# Sheet1.net
KiCad netlist of a schematic drawn in Altium Designer
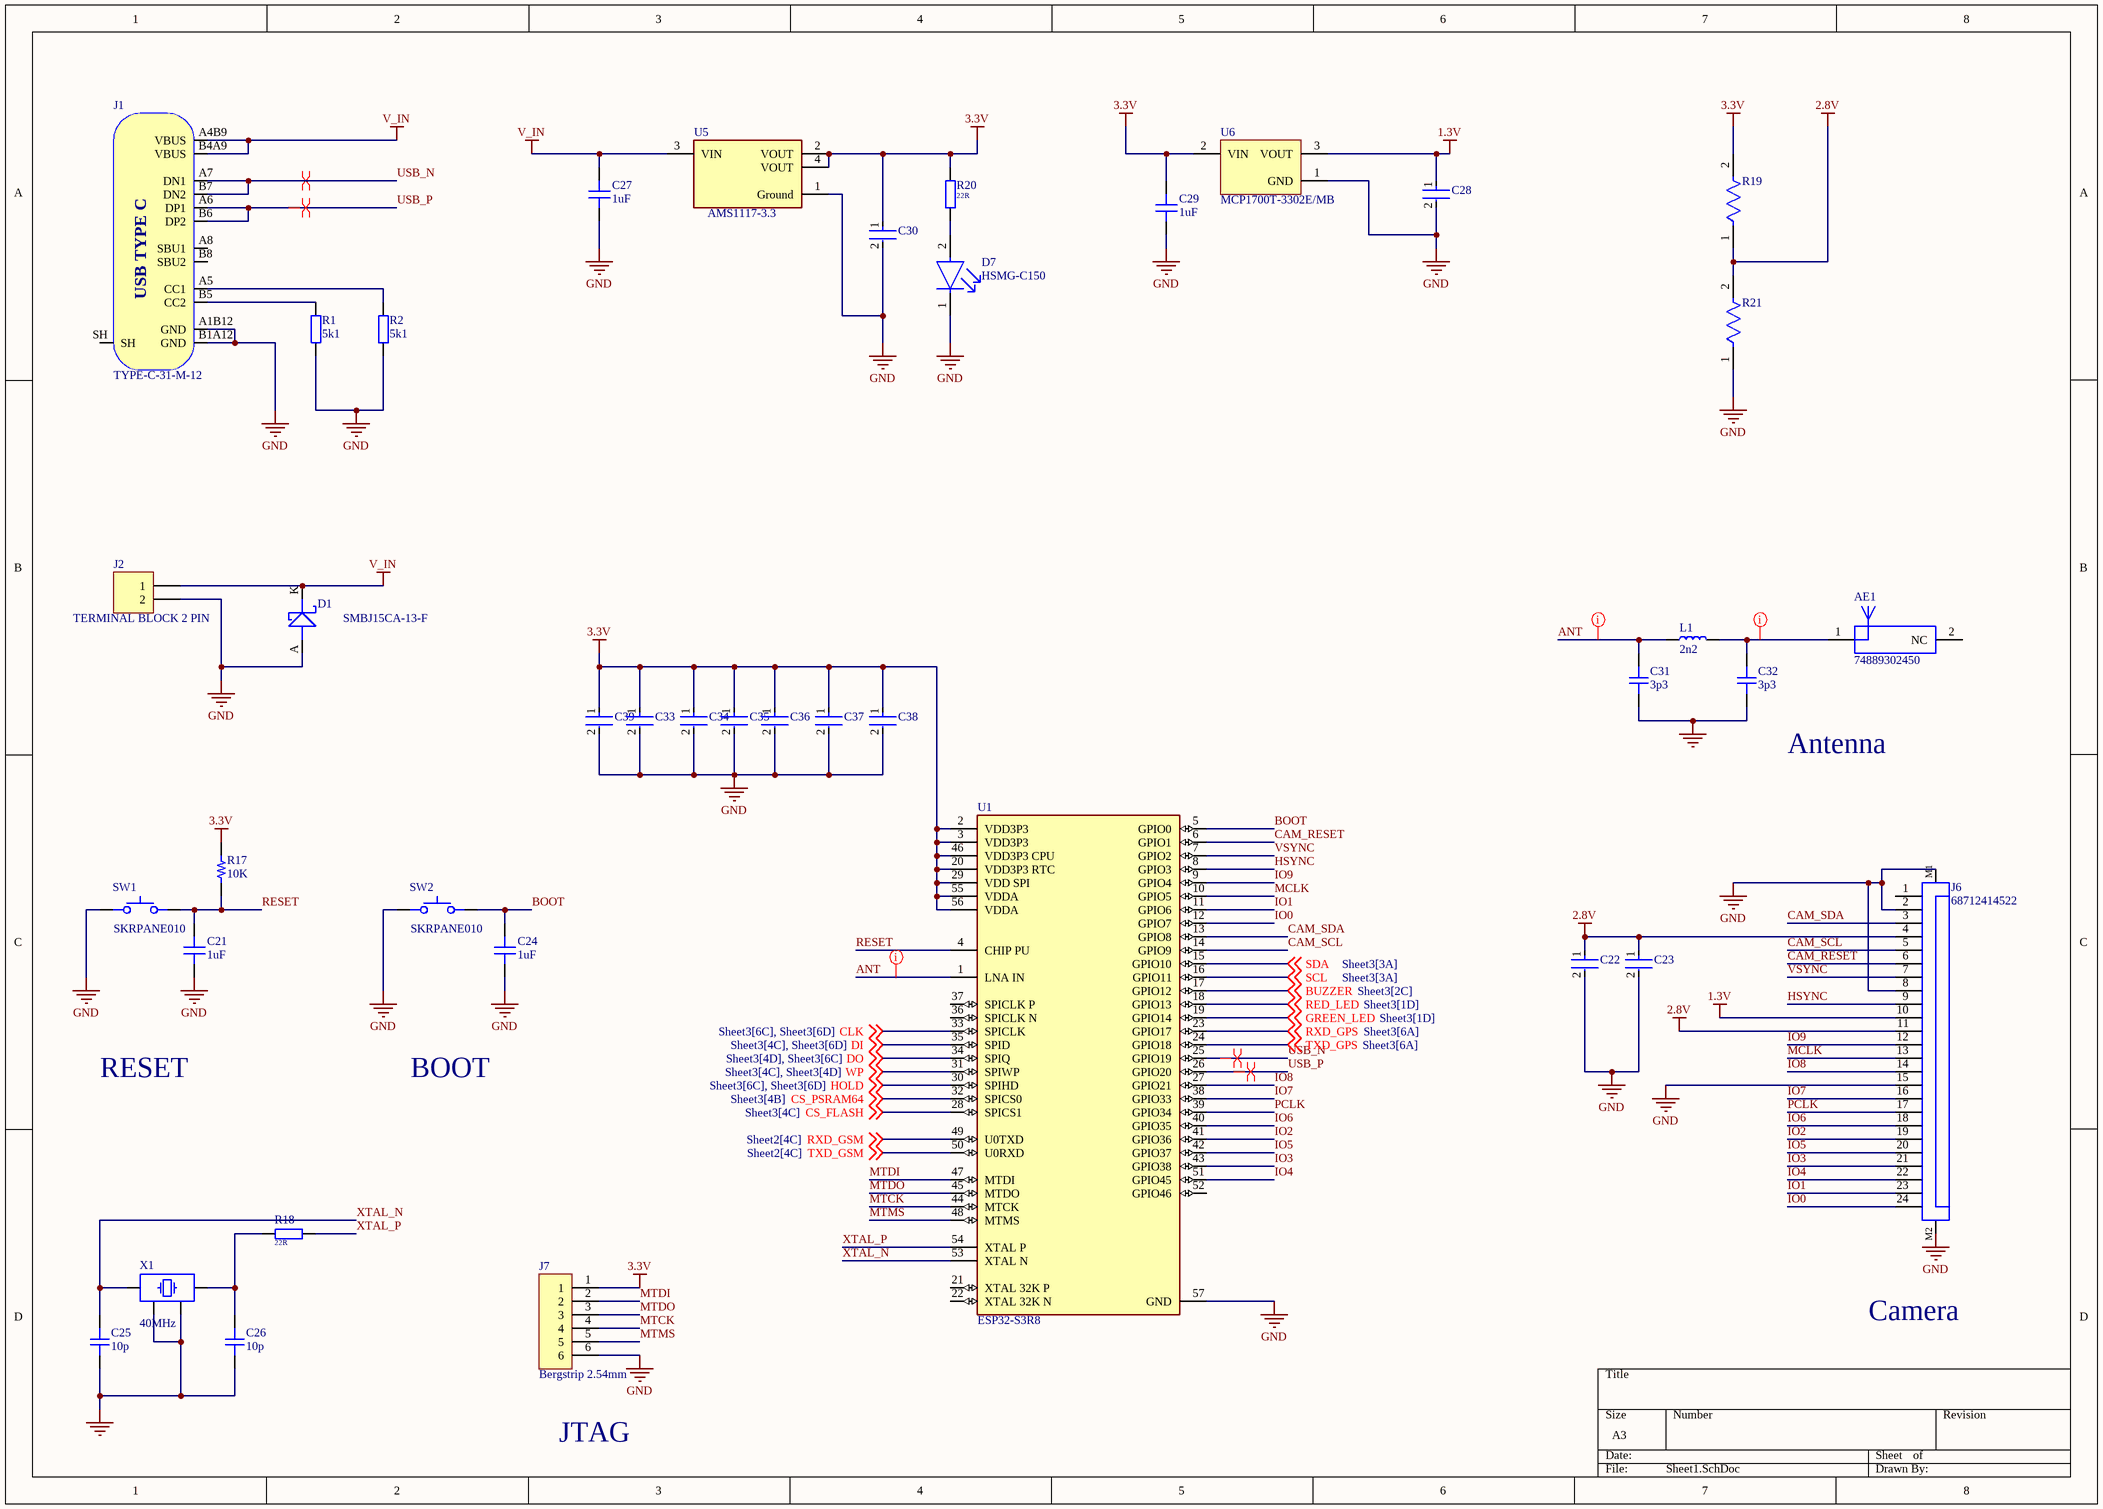
[diagram p0: Sheet1.SchDoc]

(export (version "E")
  (design (tool "Eeschema 10.0.6"))
  (components
    (comp (ref "AE1")
      (value "74889302450")
      (footprint "74889302450")
      (description "74889302450 Chip Antenna, 2.45Ghz, 3.2Mm X 1.6Mm X 1.2Mm Rohs Compliant: Yes")
      (libsource (lib "Altium Content Vault") (part "74889302450"))
    )
    (comp (ref "C21")
      (value "1uF")
      (footprint "CAP 0402_1005")
      (description "SMT Capacitor")
      (libsource (lib "Capacitor") (part "Cap 0402"))
    )
    (comp (ref "C22")
      (value "C0402C104K4RACTU")
      (footprint "FP-C0402-BB-MFG")
      (description "CAP CER 0.1UF 16V X7R 0402")
      (fields
        (field (name "TOLERANCE") "0.1")
        (field (name "OCTOPART") "https://octopart.com/c0402c104k4ractu-kemet-94158")
      )
      (libsource (lib "Altium Content Vault") (part "b4654b650e69147ec39a6b967a45e02"))
    )
    (comp (ref "C23")
      (value "C0402C104K4RACTU")
      (footprint "FP-C0402-BB-MFG")
      (description "CAP CER 0.1UF 16V X7R 0402")
      (fields
        (field (name "TOLERANCE") "0.1")
        (field (name "OCTOPART") "https://octopart.com/c0402c104k4ractu-kemet-94158")
      )
      (libsource (lib "Altium Content Vault") (part "b4654b650e69147ec39a6b967a45e02"))
    )
    (comp (ref "C24")
      (value "1uF")
      (footprint "CAP 0402_1005")
      (description "SMT Capacitor")
      (libsource (lib "Capacitor") (part "Cap 0402"))
    )
    (comp (ref "C25")
      (value "10p")
      (footprint "CAP_0402")
      (description "Capacitor SMD 0402 50V")
      (fields
        (field (name "MANUFACTURER") "Samsung")
        (field (name "MANUFACTURER PART NUMBER") "CL05C100JB5NNNC")
      )
      (libsource (lib "Schematic-Lib-PhilsLab") (part "CAP_0402_50V"))
    )
    (comp (ref "C26")
      (value "10p")
      (footprint "CAP_0402")
      (description "Capacitor SMD 0402 50V")
      (fields
        (field (name "MANUFACTURER") "Samsung")
        (field (name "MANUFACTURER PART NUMBER") "CL05C100JB5NNNC")
      )
      (libsource (lib "Schematic-Lib-PhilsLab") (part "CAP_0402_50V"))
    )
    (comp (ref "C27")
      (value "1uF")
      (footprint "CAP 0402_1005")
      (description "SMT Capacitor")
      (libsource (lib "Capacitor") (part "Cap 0402"))
    )
    (comp (ref "C28")
      (value "C0402C104K4RACTU")
      (footprint "FP-C0402-BB-MFG")
      (description "CAP CER 0.1UF 16V X7R 0402")
      (fields
        (field (name "TOLERANCE") "0.1")
        (field (name "OCTOPART") "https://octopart.com/c0402c104k4ractu-kemet-94158")
      )
      (libsource (lib "Altium Content Vault") (part "b4654b650e69147ec39a6b967a45e02"))
    )
    (comp (ref "C29")
      (value "1uF")
      (footprint "CAP 0402_1005")
      (description "SMT Capacitor")
      (libsource (lib "Capacitor") (part "Cap 0402"))
    )
    (comp (ref "C30")
      (value "C0402C104K4RACTU")
      (footprint "FP-C0402-BB-MFG")
      (description "CAP CER 0.1UF 16V X7R 0402")
      (fields
        (field (name "TOLERANCE") "0.1")
        (field (name "OCTOPART") "https://octopart.com/c0402c104k4ractu-kemet-94158")
      )
      (libsource (lib "Altium Content Vault") (part "b4654b650e69147ec39a6b967a45e02"))
    )
    (comp (ref "C31")
      (value "3p3")
      (footprint "CAP_0402")
      (description "Capacitor SMD 0402 50V")
      (fields (field (name "MANUFACTURER") "FH") (field (name "MANUFACTURER PART NUMBER") "0402CG3R3C500NT"))
      (libsource (lib "Schematic-Lib-PhilsLab") (part "CAP_0402_50V"))
    )
    (comp (ref "C32")
      (value "3p3")
      (footprint "CAP_0402")
      (description "Capacitor SMD 0402 50V")
      (fields (field (name "MANUFACTURER") "FH") (field (name "MANUFACTURER PART NUMBER") "0402CG3R3C500NT"))
      (libsource (lib "Schematic-Lib-PhilsLab") (part "CAP_0402_50V"))
    )
    (comp (ref "C33")
      (value "C0402C104K4RACTU")
      (footprint "FP-C0402-BB-MFG")
      (description "CAP CER 0.1UF 16V X7R 0402")
      (fields
        (field (name "TOLERANCE") "0.1")
        (field (name "OCTOPART") "https://octopart.com/c0402c104k4ractu-kemet-94158")
      )
      (libsource (lib "Altium Content Vault") (part "b4654b650e69147ec39a6b967a45e02"))
    )
    (comp (ref "C34")
      (value "C0402C104K4RACTU")
      (footprint "FP-C0402-BB-MFG")
      (description "CAP CER 0.1UF 16V X7R 0402")
      (fields
        (field (name "TOLERANCE") "0.1")
        (field (name "OCTOPART") "https://octopart.com/c0402c104k4ractu-kemet-94158")
      )
      (libsource (lib "Altium Content Vault") (part "b4654b650e69147ec39a6b967a45e02"))
    )
    (comp (ref "C35")
      (value "C0402C104K4RACTU")
      (footprint "FP-C0402-BB-MFG")
      (description "CAP CER 0.1UF 16V X7R 0402")
      (fields
        (field (name "TOLERANCE") "0.1")
        (field (name "OCTOPART") "https://octopart.com/c0402c104k4ractu-kemet-94158")
      )
      (libsource (lib "Altium Content Vault") (part "b4654b650e69147ec39a6b967a45e02"))
    )
    (comp (ref "C36")
      (value "C0402C104K4RACTU")
      (footprint "FP-C0402-BB-MFG")
      (description "CAP CER 0.1UF 16V X7R 0402")
      (fields
        (field (name "TOLERANCE") "0.1")
        (field (name "OCTOPART") "https://octopart.com/c0402c104k4ractu-kemet-94158")
      )
      (libsource (lib "Altium Content Vault") (part "b4654b650e69147ec39a6b967a45e02"))
    )
    (comp (ref "C37")
      (value "C0402C104K4RACTU")
      (footprint "FP-C0402-BB-MFG")
      (description "CAP CER 0.1UF 16V X7R 0402")
      (fields
        (field (name "TOLERANCE") "0.1")
        (field (name "OCTOPART") "https://octopart.com/c0402c104k4ractu-kemet-94158")
      )
      (libsource (lib "Altium Content Vault") (part "b4654b650e69147ec39a6b967a45e02"))
    )
    (comp (ref "C38")
      (value "C0402C104K4RACTU")
      (footprint "FP-C0402-BB-MFG")
      (description "CAP CER 0.1UF 16V X7R 0402")
      (fields
        (field (name "TOLERANCE") "0.1")
        (field (name "OCTOPART") "https://octopart.com/c0402c104k4ractu-kemet-94158")
      )
      (libsource (lib "Altium Content Vault") (part "b4654b650e69147ec39a6b967a45e02"))
    )
    (comp (ref "C39")
      (value "C0402C104K4RACTU")
      (footprint "FP-C0402-BB-MFG")
      (description "CAP CER 0.1UF 16V X7R 0402")
      (fields
        (field (name "TOLERANCE") "0.1")
        (field (name "OCTOPART") "https://octopart.com/c0402c104k4ractu-kemet-94158")
      )
      (libsource (lib "Altium Content Vault") (part "b4654b650e69147ec39a6b967a45e02"))
    )
    (comp (ref "D1")
      (value "SMBJ15CA-13-F")
      (footprint "DIO_SMB_DO-214AA")
      (description "24.4V Clamp 24.6A Ipp Tvs Diode Surface Mount DO-214AA (SMBJ)")
      (fields (field (name "MANUFACTURER") "Nexperia"))
      (libsource (lib "ESTEEMPCBLIB") (part "DIO-T_15V-24V-24.6A-DO214AA"))
    )
    (comp (ref "D7")
      (value "HSMG-C150")
      (footprint "FP-HSMG-C150-MFG")
      (description "LED GREEN DIFFUSED 1206 SMD")
      (fields
        (field (name "MANUFACTURER") "Broadcom")
        (field (name "OCTOPART") "https://octopart.com/hsmg-c150-broadcom-71131304")
      )
      (libsource (lib "Altium Content Vault") (part "8706943c75ba83719d021d2fdc84c58"))
    )
    (comp (ref "J1")
      (value "TYPE-C-31-M-12")
      (footprint "TYPE-C-31-M-12")
      (description "USB Type C Connector Horizontal SMT")
      (fields (field (name "MANUFACTURER") "Koren Hroparts"))
      (libsource (lib "ESP32_USB_Dongle") (part "TYPE-C-31-M-12"))
    )
    (comp (ref "J2")
      (value "TERMINAL BLOCK 2 PIN")
      (footprint "CON2_P196_1729128_TH_ST")
      (description "2 Pins, 1 Row 5mm Pitch, straight Connector, male")
      (fields
        (field (name "MANUFACTURER") "Phoenix Contact")
        (field (name "MANUFACTURER PART NUMBER") "MKDSN1,5/2")
      )
      (libsource (lib "ESTEEMPCBLIB") (part "CON-TB_2X1-196-ST-TH"))
    )
    (comp (ref "J6")
      (value "68712414522")
      (footprint "68712414522")
      (libsource (lib "Altium Content Vault") (part "FPC - 24P - 2MP"))
    )
    (comp (ref "J7")
      (value "Bergstrip 2.54mm")
      (footprint "CON6_100_59D78_TH_ST")
      (description "6 Pins, 1 Row 2.54mm Pitch, Straight bergstrip, Female")
      (fields (field (name "MANUFACTURER") "Molex") (field (name "MANUFACTURER PART NUMBER") "22-10-2061"))
      (libsource (lib "ESTEEMPCBLIB") (part "CON-BS-SKT_6X1-100-ST-TH"))
    )
    (comp (ref "L1")
      (value "2n2")
      (footprint "IND_0402")
      (description "Inductor SMD 0402")
      (fields
        (field (name "MANUFACTURER") "Murata")
        (field (name "MANUFACTURER PART NUMBER") "LQW15AN2N2G80D")
      )
      (libsource (lib "Schematic-Lib-PhilsLab") (part "IND_0402"))
    )
    (comp (ref "R1")
      (value "5k1")
      (footprint "RES_0402")
      (description "Resistor SMD 0402")
      (fields
        (field (name "MANUFACTURER") "YAGEO")
        (field (name "MANUFACTURER PART NUMBER") "RC0402JR-075K1L")
      )
      (libsource (lib "ESP32_USB_Dongle") (part "RES_0402"))
    )
    (comp (ref "R2")
      (value "5k1")
      (footprint "RES_0402")
      (description "Resistor SMD 0402")
      (fields
        (field (name "MANUFACTURER") "YAGEO")
        (field (name "MANUFACTURER PART NUMBER") "RC0402JR-075K1L")
      )
      (libsource (lib "ESP32_USB_Dongle") (part "RES_0402"))
    )
    (comp (ref "R17")
      (value "10K")
      (footprint "RES 0402_1005")
      (description "SMT Resistor")
      (libsource (lib "Resistor") (part "Res 0402"))
    )
    (comp (ref "R18")
      (value "22R")
      (footprint "RES_0402")
      (description "Resistor SMD 0402")
      (fields
        (field (name "MANUFACTURER") "UNI-ROYAL")
        (field (name "MANUFACTURER PART NUMBER") "0402WGF220JTCE")
      )
      (libsource (lib "Schematic-Lib-PhilsLab") (part "RES_0402"))
    )
    (comp (ref "R19")
      (value "CRCW06031K00FKEA")
      (footprint "FP-CRCW0603-e3-MFG")
      (description "RES Thick Film, 1kΩ, 1%, 0.1W, 100ppm/°C, 0603")
      (fields (field (name "TOLERANCE") "1%"))
      (libsource (lib "Altium Content Vault") (part "1029c3af85768c4190bb7ad29bc67b5"))
    )
    (comp (ref "R20")
      (value "22R")
      (footprint "RES_0402")
      (description "Resistor SMD 0402")
      (fields
        (field (name "MANUFACTURER") "UNI-ROYAL")
        (field (name "MANUFACTURER PART NUMBER") "0402WGF220JTCE")
      )
      (libsource (lib "Schematic-Lib-PhilsLab") (part "RES_0402"))
    )
    (comp (ref "R21")
      (value "CRCW06035K60FKEA")
      (footprint "FP-CRCW0603-e3-MFG")
      (description "RES Thick Film, 5.6kΩ, 1%, 0.1W, 100ppm/°C, 0603")
      (fields (field (name "TOLERANCE") "1%"))
      (libsource (lib "Altium Content Vault") (part "1029c3af85768c4190bb7ad29bc67b5"))
    )
    (comp (ref "SW1")
      (value "SKRPANE010")
      (footprint "SKRPANE010")
      (description "Tactile Switch SMD SPST")
      (fields (field (name "MANUFACTURER") "Alps Alpine"))
      (libsource (lib "ESP32_USB_Dongle") (part "SKRPANE010"))
    )
    (comp (ref "SW2")
      (value "SKRPANE010")
      (footprint "SKRPANE010")
      (description "Tactile Switch SMD SPST")
      (fields (field (name "MANUFACTURER") "Alps Alpine"))
      (libsource (lib "ESP32_USB_Dongle") (part "SKRPANE010"))
    )
    (comp (ref "U1")
      (value "ESP32-S3R8")
      (footprint "FP-ESP32-S3R8-IPC_A")
      (description "ESP32-S3R8 RF System on a Chip - SoC SMD IC, Dual-Core MCU, Wi-Fi 2.4G BLE 5.0 Combo")
      (libsource (lib "Altium Content Vault") (part "a095f160bb9f313373d963ad131b0ed"))
    )
    (comp (ref "U5")
      (value "AMS1117-3.3")
      (footprint "FP-AMS1117-IPC_C")
      (description "LDO Voltage Regulators 1A, 3.3V")
      (fields
        (field (name "OCTOPART") "https://octopart.com/ams1117-3.3-advanced+monolithic+systems-25899300")
        (field (name "MANUFACTURER") "Advanced Monolithic Systems")
      )
      (libsource (lib "Altium Content Vault") (part "8bdbb5f8e77002000e30dd2845d0354"))
    )
    (comp (ref "U6")
      (value "MCP1700T-3302E/MB")
      (footprint "SOT-89-MB3_M")
      (description "Low Quiescent Current LDO, 3-Pin SOT-89, Extended Temperature, Tape and Reel")
      (libsource (lib "Altium Content Vault") (part "PM-LINEREG-MCP1700-IL3A"))
    )
    (comp (ref "X1")
      (value "40MHz")
      (footprint "XTAL_2520")
      (description "Crystal SMD 2520")
      (fields (field (name "MANUFACTURER") "Seiko Epson"))
      (libsource (lib "Schematic-Lib-PhilsLab") (part "XTAL_2520"))
    )
  )
  (nets
    (net (code "1") (name "/ANT") (class "Default")
      (node (ref "C31") (pin "2") (pinfunction "2_2") (pintype "passive"))
      (node (ref "L1") (pin "2") (pinfunction "2_2") (pintype "passive"))
      (node (ref "U1") (pin "1") (pinfunction "LNA_IN_1") (pintype "passive"))
    )
    (net (code "2") (name "/BOOT") (class "Default")
      (node (ref "C24") (pin "2") (pinfunction "2_2") (pintype "passive"))
      (node (ref "SW2") (pin "34") (pintype "passive"))
      (node (ref "U1") (pin "5") (pinfunction "GPIO0_5") (pintype "bidirectional"))
    )
    (net (code "3") (name "/CAM_RESET") (class "Default")
      (node (ref "J6") (pin "6") (pinfunction "6_6") (pintype "passive"))
      (node (ref "U1") (pin "6") (pinfunction "GPIO1_6") (pintype "bidirectional"))
    )
    (net (code "4") (name "/CAM_SCL") (class "Default")
      (node (ref "J6") (pin "5") (pinfunction "5_5") (pintype "passive"))
      (node (ref "U1") (pin "14") (pinfunction "GPIO9_14") (pintype "bidirectional"))
    )
    (net (code "5") (name "/CAM_SDA") (class "Default")
      (node (ref "J6") (pin "3") (pinfunction "3_3") (pintype "passive"))
      (node (ref "U1") (pin "13") (pinfunction "GPIO8_13") (pintype "bidirectional"))
    )
    (net (code "6") (name "/HSYNC") (class "Default")
      (node (ref "J6") (pin "9") (pinfunction "9_9") (pintype "passive"))
      (node (ref "U1") (pin "8") (pinfunction "GPIO3_8") (pintype "bidirectional"))
    )
    (net (code "7") (name "/IO0") (class "Default")
      (node (ref "J6") (pin "24") (pinfunction "24_24") (pintype "passive"))
      (node (ref "U1") (pin "12") (pinfunction "GPIO7_12") (pintype "bidirectional"))
    )
    (net (code "8") (name "/IO1") (class "Default")
      (node (ref "J6") (pin "23") (pinfunction "23_23") (pintype "passive"))
      (node (ref "U1") (pin "11") (pinfunction "GPIO6_11") (pintype "bidirectional"))
    )
    (net (code "9") (name "/IO2") (class "Default")
      (node (ref "J6") (pin "19") (pinfunction "19_19") (pintype "passive"))
      (node (ref "U1") (pin "41") (pinfunction "GPIO36_41") (pintype "bidirectional"))
    )
    (net (code "10") (name "/IO3") (class "Default")
      (node (ref "J6") (pin "21") (pinfunction "21_21") (pintype "passive"))
      (node (ref "U1") (pin "43") (pinfunction "GPIO38_43") (pintype "bidirectional"))
    )
    (net (code "11") (name "/IO4") (class "Default")
      (node (ref "J6") (pin "22") (pinfunction "22_22") (pintype "passive"))
      (node (ref "U1") (pin "51") (pinfunction "GPIO45_51") (pintype "bidirectional"))
    )
    (net (code "12") (name "/IO5") (class "Default")
      (node (ref "J6") (pin "20") (pinfunction "20_20") (pintype "passive"))
      (node (ref "U1") (pin "42") (pinfunction "GPIO37_42") (pintype "bidirectional"))
    )
    (net (code "13") (name "/IO6") (class "Default")
      (node (ref "J6") (pin "18") (pinfunction "18_18") (pintype "passive"))
      (node (ref "U1") (pin "40") (pinfunction "GPIO35_40") (pintype "bidirectional"))
    )
    (net (code "14") (name "/IO7") (class "Default")
      (node (ref "J6") (pin "16") (pinfunction "16_16") (pintype "passive"))
      (node (ref "U1") (pin "38") (pinfunction "GPIO33_38") (pintype "bidirectional"))
    )
    (net (code "15") (name "/IO8") (class "Default")
      (node (ref "J6") (pin "14") (pinfunction "14_14") (pintype "passive"))
      (node (ref "U1") (pin "27") (pinfunction "GPIO21_27") (pintype "bidirectional"))
    )
    (net (code "16") (name "/IO9") (class "Default")
      (node (ref "J6") (pin "12") (pinfunction "12_12") (pintype "passive"))
      (node (ref "U1") (pin "9") (pinfunction "GPIO4_9") (pintype "bidirectional"))
    )
    (net (code "17") (name "/MCLK") (class "Default")
      (node (ref "J6") (pin "13") (pinfunction "13_13") (pintype "passive"))
      (node (ref "U1") (pin "10") (pinfunction "GPIO5_10") (pintype "bidirectional"))
    )
    (net (code "18") (name "/MTCK") (class "Default")
      (node (ref "J7") (pin "4") (pinfunction "4_4") (pintype "passive"))
      (node (ref "U1") (pin "44") (pinfunction "MTCK_44") (pintype "bidirectional"))
    )
    (net (code "19") (name "/MTDI") (class "Default")
      (node (ref "J7") (pin "2") (pinfunction "2_2") (pintype "passive"))
      (node (ref "U1") (pin "47") (pinfunction "MTDI_47") (pintype "bidirectional"))
    )
    (net (code "20") (name "/MTDO") (class "Default")
      (node (ref "J7") (pin "3") (pinfunction "3_3") (pintype "passive"))
      (node (ref "U1") (pin "45") (pinfunction "MTDO_45") (pintype "bidirectional"))
    )
    (net (code "21") (name "/MTMS") (class "Default")
      (node (ref "J7") (pin "5") (pinfunction "5_5") (pintype "passive"))
      (node (ref "U1") (pin "48") (pinfunction "MTMS_48") (pintype "bidirectional"))
    )
    (net (code "22") (name "/PCLK") (class "Default")
      (node (ref "J6") (pin "17") (pinfunction "17_17") (pintype "passive"))
      (node (ref "U1") (pin "39") (pinfunction "GPIO34_39") (pintype "bidirectional"))
    )
    (net (code "23") (name "/RESET") (class "Default")
      (node (ref "C21") (pin "2") (pinfunction "2_2") (pintype "passive"))
      (node (ref "R17") (pin "1") (pinfunction "1_1") (pintype "passive"))
      (node (ref "SW1") (pin "34") (pintype "passive"))
      (node (ref "U1") (pin "4") (pinfunction "CHIP_PU_4") (pintype "passive"))
    )
    (net (code "24") (name "/USB_N") (class "Default")
      (node (ref "J1") (pin "A7") (pinfunction "DN1_A7") (pintype "bidirectional"))
      (node (ref "J1") (pin "B7") (pinfunction "DN2_B7") (pintype "bidirectional"))
      (node (ref "U1") (pin "25") (pinfunction "GPIO19_25") (pintype "bidirectional"))
    )
    (net (code "25") (name "/USB_P") (class "Default")
      (node (ref "J1") (pin "A6") (pinfunction "DP1_A6") (pintype "bidirectional"))
      (node (ref "J1") (pin "B6") (pinfunction "DP2_B6") (pintype "bidirectional"))
      (node (ref "U1") (pin "26") (pinfunction "GPIO20_26") (pintype "bidirectional"))
    )
    (net (code "26") (name "/VSYNC") (class "Default")
      (node (ref "J6") (pin "7") (pinfunction "7_7") (pintype "passive"))
      (node (ref "U1") (pin "7") (pinfunction "GPIO2_7") (pintype "bidirectional"))
    )
    (net (code "27") (name "/XTAL_N") (class "Default")
      (node (ref "C25") (pin "2") (pinfunction "2_2") (pintype "passive"))
      (node (ref "U1") (pin "53") (pinfunction "XTAL_N_53") (pintype "passive"))
      (node (ref "X1") (pin "1") (pinfunction "1_1") (pintype "passive"))
    )
    (net (code "28") (name "/XTAL_P") (class "Default")
      (node (ref "R18") (pin "1") (pinfunction "1_1") (pintype "passive"))
      (node (ref "U1") (pin "54") (pinfunction "XTAL_P_54") (pintype "passive"))
    )
    (net (code "29") (name "1.3V") (class "Default")
      (node (ref "C28") (pin "1") (pinfunction "1_1") (pintype "passive"))
      (node (ref "J6") (pin "10") (pinfunction "10_10") (pintype "passive"))
      (node (ref "U6") (pin "3") (pinfunction "VOUT_3") (pintype "power_in"))
    )
    (net (code "30") (name "2.8V") (class "Default")
      (node (ref "C22") (pin "1") (pinfunction "1_1") (pintype "passive"))
      (node (ref "C23") (pin "1") (pinfunction "1_1") (pintype "passive"))
      (node (ref "J6") (pin "11") (pinfunction "11_11") (pintype "passive"))
      (node (ref "J6") (pin "4") (pinfunction "4_4") (pintype "passive"))
      (node (ref "R19") (pin "1") (pinfunction "1_1") (pintype "passive"))
      (node (ref "R21") (pin "2") (pinfunction "2_2") (pintype "passive"))
    )
    (net (code "31") (name "3.3V") (class "Default")
      (node (ref "C29") (pin "2") (pinfunction "2_2") (pintype "passive"))
      (node (ref "C30") (pin "1") (pinfunction "1_1") (pintype "passive"))
      (node (ref "C33") (pin "1") (pinfunction "1_1") (pintype "passive"))
      (node (ref "C34") (pin "1") (pinfunction "1_1") (pintype "passive"))
      (node (ref "C35") (pin "1") (pinfunction "1_1") (pintype "passive"))
      (node (ref "C36") (pin "1") (pinfunction "1_1") (pintype "passive"))
      (node (ref "C37") (pin "1") (pinfunction "1_1") (pintype "passive"))
      (node (ref "C38") (pin "1") (pinfunction "1_1") (pintype "passive"))
      (node (ref "C39") (pin "1") (pinfunction "1_1") (pintype "passive"))
      (node (ref "J7") (pin "1") (pinfunction "1_1") (pintype "passive"))
      (node (ref "R17") (pin "2") (pinfunction "2_2") (pintype "passive"))
      (node (ref "R19") (pin "2") (pinfunction "2_2") (pintype "passive"))
      (node (ref "R20") (pin "1") (pinfunction "1_1") (pintype "passive"))
      (node (ref "U1") (pin "2") (pinfunction "VDD3P3_2") (pintype "power_in"))
      (node (ref "U1") (pin "20") (pinfunction "VDD3P3_RTC_20") (pintype "power_in"))
      (node (ref "U1") (pin "29") (pinfunction "VDD_SPI_29") (pintype "power_in"))
      (node (ref "U1") (pin "3") (pinfunction "VDD3P3_3") (pintype "power_in"))
      (node (ref "U1") (pin "46") (pinfunction "VDD3P3_CPU_46") (pintype "power_in"))
      (node (ref "U1") (pin "55") (pinfunction "VDDA_55") (pintype "power_in"))
      (node (ref "U1") (pin "56") (pinfunction "VDDA_56") (pintype "power_in"))
      (node (ref "U5") (pin "2") (pinfunction "VOUT_2") (pintype "passive"))
      (node (ref "U5") (pin "4") (pinfunction "VOUT_4") (pintype "passive"))
      (node (ref "U6") (pin "2") (pinfunction "VIN_2") (pintype "power_in"))
    )
    (net (code "32") (name "BUZZER") (class "Default")
      (node (ref "U1") (pin "17") (pinfunction "GPIO12_17") (pintype "bidirectional"))
    )
    (net (code "33") (name "CLK") (class "Default")
      (node (ref "U1") (pin "33") (pinfunction "SPICLK_33") (pintype "bidirectional"))
    )
    (net (code "34") (name "CS_FLASH") (class "Default")
      (node (ref "U1") (pin "28") (pinfunction "SPICS1_28") (pintype "bidirectional"))
    )
    (net (code "35") (name "CS_PSRAM64") (class "Default")
      (node (ref "U1") (pin "32") (pinfunction "SPICS0_32") (pintype "bidirectional"))
    )
    (net (code "36") (name "DI") (class "Default")
      (node (ref "U1") (pin "35") (pinfunction "SPID_35") (pintype "bidirectional"))
    )
    (net (code "37") (name "DO") (class "Default")
      (node (ref "U1") (pin "34") (pinfunction "SPIQ_34") (pintype "bidirectional"))
    )
    (net (code "38") (name "GND") (class "Default")
      (node (ref "C21") (pin "1") (pinfunction "1_1") (pintype "passive"))
      (node (ref "C22") (pin "2") (pinfunction "2_2") (pintype "passive"))
      (node (ref "C23") (pin "2") (pinfunction "2_2") (pintype "passive"))
      (node (ref "C24") (pin "1") (pinfunction "1_1") (pintype "passive"))
      (node (ref "C25") (pin "1") (pinfunction "1_1") (pintype "passive"))
      (node (ref "C26") (pin "1") (pinfunction "1_1") (pintype "passive"))
      (node (ref "C27") (pin "1") (pinfunction "1_1") (pintype "passive"))
      (node (ref "C28") (pin "2") (pinfunction "2_2") (pintype "passive"))
      (node (ref "C29") (pin "1") (pinfunction "1_1") (pintype "passive"))
      (node (ref "C30") (pin "2") (pinfunction "2_2") (pintype "passive"))
      (node (ref "C31") (pin "1") (pinfunction "1_1") (pintype "passive"))
      (node (ref "C32") (pin "1") (pinfunction "1_1") (pintype "passive"))
      (node (ref "C33") (pin "2") (pinfunction "2_2") (pintype "passive"))
      (node (ref "C34") (pin "2") (pinfunction "2_2") (pintype "passive"))
      (node (ref "C35") (pin "2") (pinfunction "2_2") (pintype "passive"))
      (node (ref "C36") (pin "2") (pinfunction "2_2") (pintype "passive"))
      (node (ref "C37") (pin "2") (pinfunction "2_2") (pintype "passive"))
      (node (ref "C38") (pin "2") (pinfunction "2_2") (pintype "passive"))
      (node (ref "C39") (pin "2") (pinfunction "2_2") (pintype "passive"))
      (node (ref "D1") (pin "A") (pinfunction "A_A") (pintype "passive"))
      (node (ref "D7") (pin "1") (pinfunction "C_1") (pintype "passive"))
      (node (ref "J1") (pin "A1B12") (pinfunction "GND_A1B12") (pintype "power_in"))
      (node (ref "J1") (pin "B1A12") (pinfunction "GND_B1A12") (pintype "power_in"))
      (node (ref "J2") (pin "2") (pinfunction "2_2") (pintype "passive"))
      (node (ref "J6") (pin "15") (pinfunction "15_15") (pintype "passive"))
      (node (ref "J6") (pin "2") (pinfunction "2_2") (pintype "passive"))
      (node (ref "J6") (pin "8") (pinfunction "8_8") (pintype "passive"))
      (node (ref "J6") (pin "M1") (pinfunction "M1_M1") (pintype "passive"))
      (node (ref "J6") (pin "M2") (pinfunction "M2_M2") (pintype "passive"))
      (node (ref "J7") (pin "6") (pinfunction "6_6") (pintype "passive"))
      (node (ref "R1") (pin "1") (pinfunction "1_1") (pintype "passive"))
      (node (ref "R2") (pin "1") (pinfunction "1_1") (pintype "passive"))
      (node (ref "R21") (pin "1") (pinfunction "1_1") (pintype "passive"))
      (node (ref "SW1") (pin "12") (pintype "passive"))
      (node (ref "SW2") (pin "12") (pintype "passive"))
      (node (ref "U1") (pin "57") (pinfunction "GND_57") (pintype "power_in"))
      (node (ref "U5") (pin "1") (pinfunction "Ground_1") (pintype "power_in"))
      (node (ref "U6") (pin "1") (pinfunction "GND_1") (pintype "power_in"))
      (node (ref "X1") (pin "2") (pinfunction "2_2") (pintype "passive"))
      (node (ref "X1") (pin "4") (pinfunction "4_4") (pintype "passive"))
    )
    (net (code "39") (name "GREEN_LED") (class "Default")
      (node (ref "U1") (pin "19") (pinfunction "GPIO14_19") (pintype "bidirectional"))
    )
    (net (code "40") (name "HOLD") (class "Default")
      (node (ref "U1") (pin "30") (pinfunction "SPIHD_30") (pintype "bidirectional"))
    )
    (net (code "41") (name "Net-(AE1-Feed)") (class "Default")
      (node (ref "AE1") (pin "1") (pinfunction "Feed_1") (pintype "passive"))
      (node (ref "C32") (pin "2") (pinfunction "2_2") (pintype "passive"))
      (node (ref "L1") (pin "1") (pinfunction "1_1") (pintype "passive"))
    )
    (net (code "42") (name "Net-(C26-Pad2)") (class "Default")
      (node (ref "C26") (pin "2") (pinfunction "2_2") (pintype "passive"))
      (node (ref "R18") (pin "2") (pinfunction "2_2") (pintype "passive"))
      (node (ref "X1") (pin "3") (pinfunction "3_3") (pintype "passive"))
    )
    (net (code "43") (name "Net-(D7-A)") (class "Default")
      (node (ref "D7") (pin "2") (pinfunction "A_2") (pintype "passive"))
      (node (ref "R20") (pin "2") (pinfunction "2_2") (pintype "passive"))
    )
    (net (code "44") (name "Net-(J1-CC1)") (class "Default")
      (node (ref "J1") (pin "A5") (pinfunction "CC1_A5") (pintype "passive"))
      (node (ref "R2") (pin "2") (pinfunction "2_2") (pintype "passive"))
    )
    (net (code "45") (name "Net-(J1-CC2)") (class "Default")
      (node (ref "J1") (pin "B5") (pinfunction "CC2_B5") (pintype "tri_state"))
      (node (ref "R1") (pin "2") (pinfunction "2_2") (pintype "passive"))
    )
    (net (code "46") (name "RED_LED") (class "Default")
      (node (ref "U1") (pin "18") (pinfunction "GPIO13_18") (pintype "bidirectional"))
    )
    (net (code "47") (name "RXD_GPS") (class "Default")
      (node (ref "U1") (pin "23") (pinfunction "GPIO17_23") (pintype "bidirectional"))
    )
    (net (code "48") (name "RXD_GSM") (class "Default")
      (node (ref "U1") (pin "49") (pinfunction "U0TXD_49") (pintype "bidirectional"))
    )
    (net (code "49") (name "SCL") (class "Default")
      (node (ref "U1") (pin "16") (pinfunction "GPIO11_16") (pintype "bidirectional"))
    )
    (net (code "50") (name "SDA") (class "Default")
      (node (ref "U1") (pin "15") (pinfunction "GPIO10_15") (pintype "bidirectional"))
    )
    (net (code "51") (name "TXD_GPS") (class "Default")
      (node (ref "U1") (pin "24") (pinfunction "GPIO18_24") (pintype "bidirectional"))
    )
    (net (code "52") (name "TXD_GSM") (class "Default")
      (node (ref "U1") (pin "50") (pinfunction "U0RXD_50") (pintype "bidirectional"))
    )
    (net (code "53") (name "V_IN") (class "Default")
      (node (ref "C27") (pin "2") (pinfunction "2_2") (pintype "passive"))
      (node (ref "D1") (pin "K") (pinfunction "K_K") (pintype "passive"))
      (node (ref "J1") (pin "A4B9") (pinfunction "VBUS_A4B9") (pintype "power_in"))
      (node (ref "J1") (pin "B4A9") (pinfunction "VBUS_B4A9") (pintype "power_in"))
      (node (ref "J2") (pin "1") (pinfunction "1_1") (pintype "passive"))
      (node (ref "U5") (pin "3") (pinfunction "VIN_3") (pintype "power_in"))
    )
    (net (code "54") (name "WP") (class "Default")
      (node (ref "U1") (pin "31") (pinfunction "SPIWP_31") (pintype "bidirectional"))
    )
    (net (code "55") (name "unconnected-(AE1-NC-Pad2)") (class "Default")
      (node (ref "AE1") (pin "2") (pinfunction "NC_2") (pintype "passive"))
    )
    (net (code "56") (name "unconnected-(J1-PadSH)") (class "Default")
      (node (ref "J1") (pin "SH") (pinfunction "SH_SH") (pintype "power_in"))
    )
    (net (code "57") (name "unconnected-(J1-SBU1-PadA8)") (class "Default")
      (node (ref "J1") (pin "A8") (pinfunction "SBU1_A8") (pintype "bidirectional"))
    )
    (net (code "58") (name "unconnected-(J1-SBU2-PadB8)") (class "Default")
      (node (ref "J1") (pin "B8") (pinfunction "SBU2_B8") (pintype "bidirectional"))
    )
    (net (code "59") (name "unconnected-(J6-Pad1)") (class "Default")
      (node (ref "J6") (pin "1") (pinfunction "1_1") (pintype "passive"))
    )
    (net (code "60") (name "unconnected-(U1-GPIO46-Pad52)") (class "Default")
      (node (ref "U1") (pin "52") (pinfunction "GPIO46_52") (pintype "bidirectional"))
    )
    (net (code "61") (name "unconnected-(U1-SPICLK_N-Pad36)") (class "Default")
      (node (ref "U1") (pin "36") (pinfunction "SPICLK_N_36") (pintype "bidirectional"))
    )
    (net (code "62") (name "unconnected-(U1-SPICLK_P-Pad37)") (class "Default")
      (node (ref "U1") (pin "37") (pinfunction "SPICLK_P_37") (pintype "bidirectional"))
    )
    (net (code "63") (name "unconnected-(U1-XTAL_32K_N-Pad22)") (class "Default")
      (node (ref "U1") (pin "22") (pinfunction "XTAL_32K_N_22") (pintype "bidirectional"))
    )
    (net (code "64") (name "unconnected-(U1-XTAL_32K_P-Pad21)") (class "Default")
      (node (ref "U1") (pin "21") (pinfunction "XTAL_32K_P_21") (pintype "bidirectional"))
    )
  )
)
